# SW6208_A_A_C_LED__188.net
KiCad netlist of a schematic drawn in Altium Designer
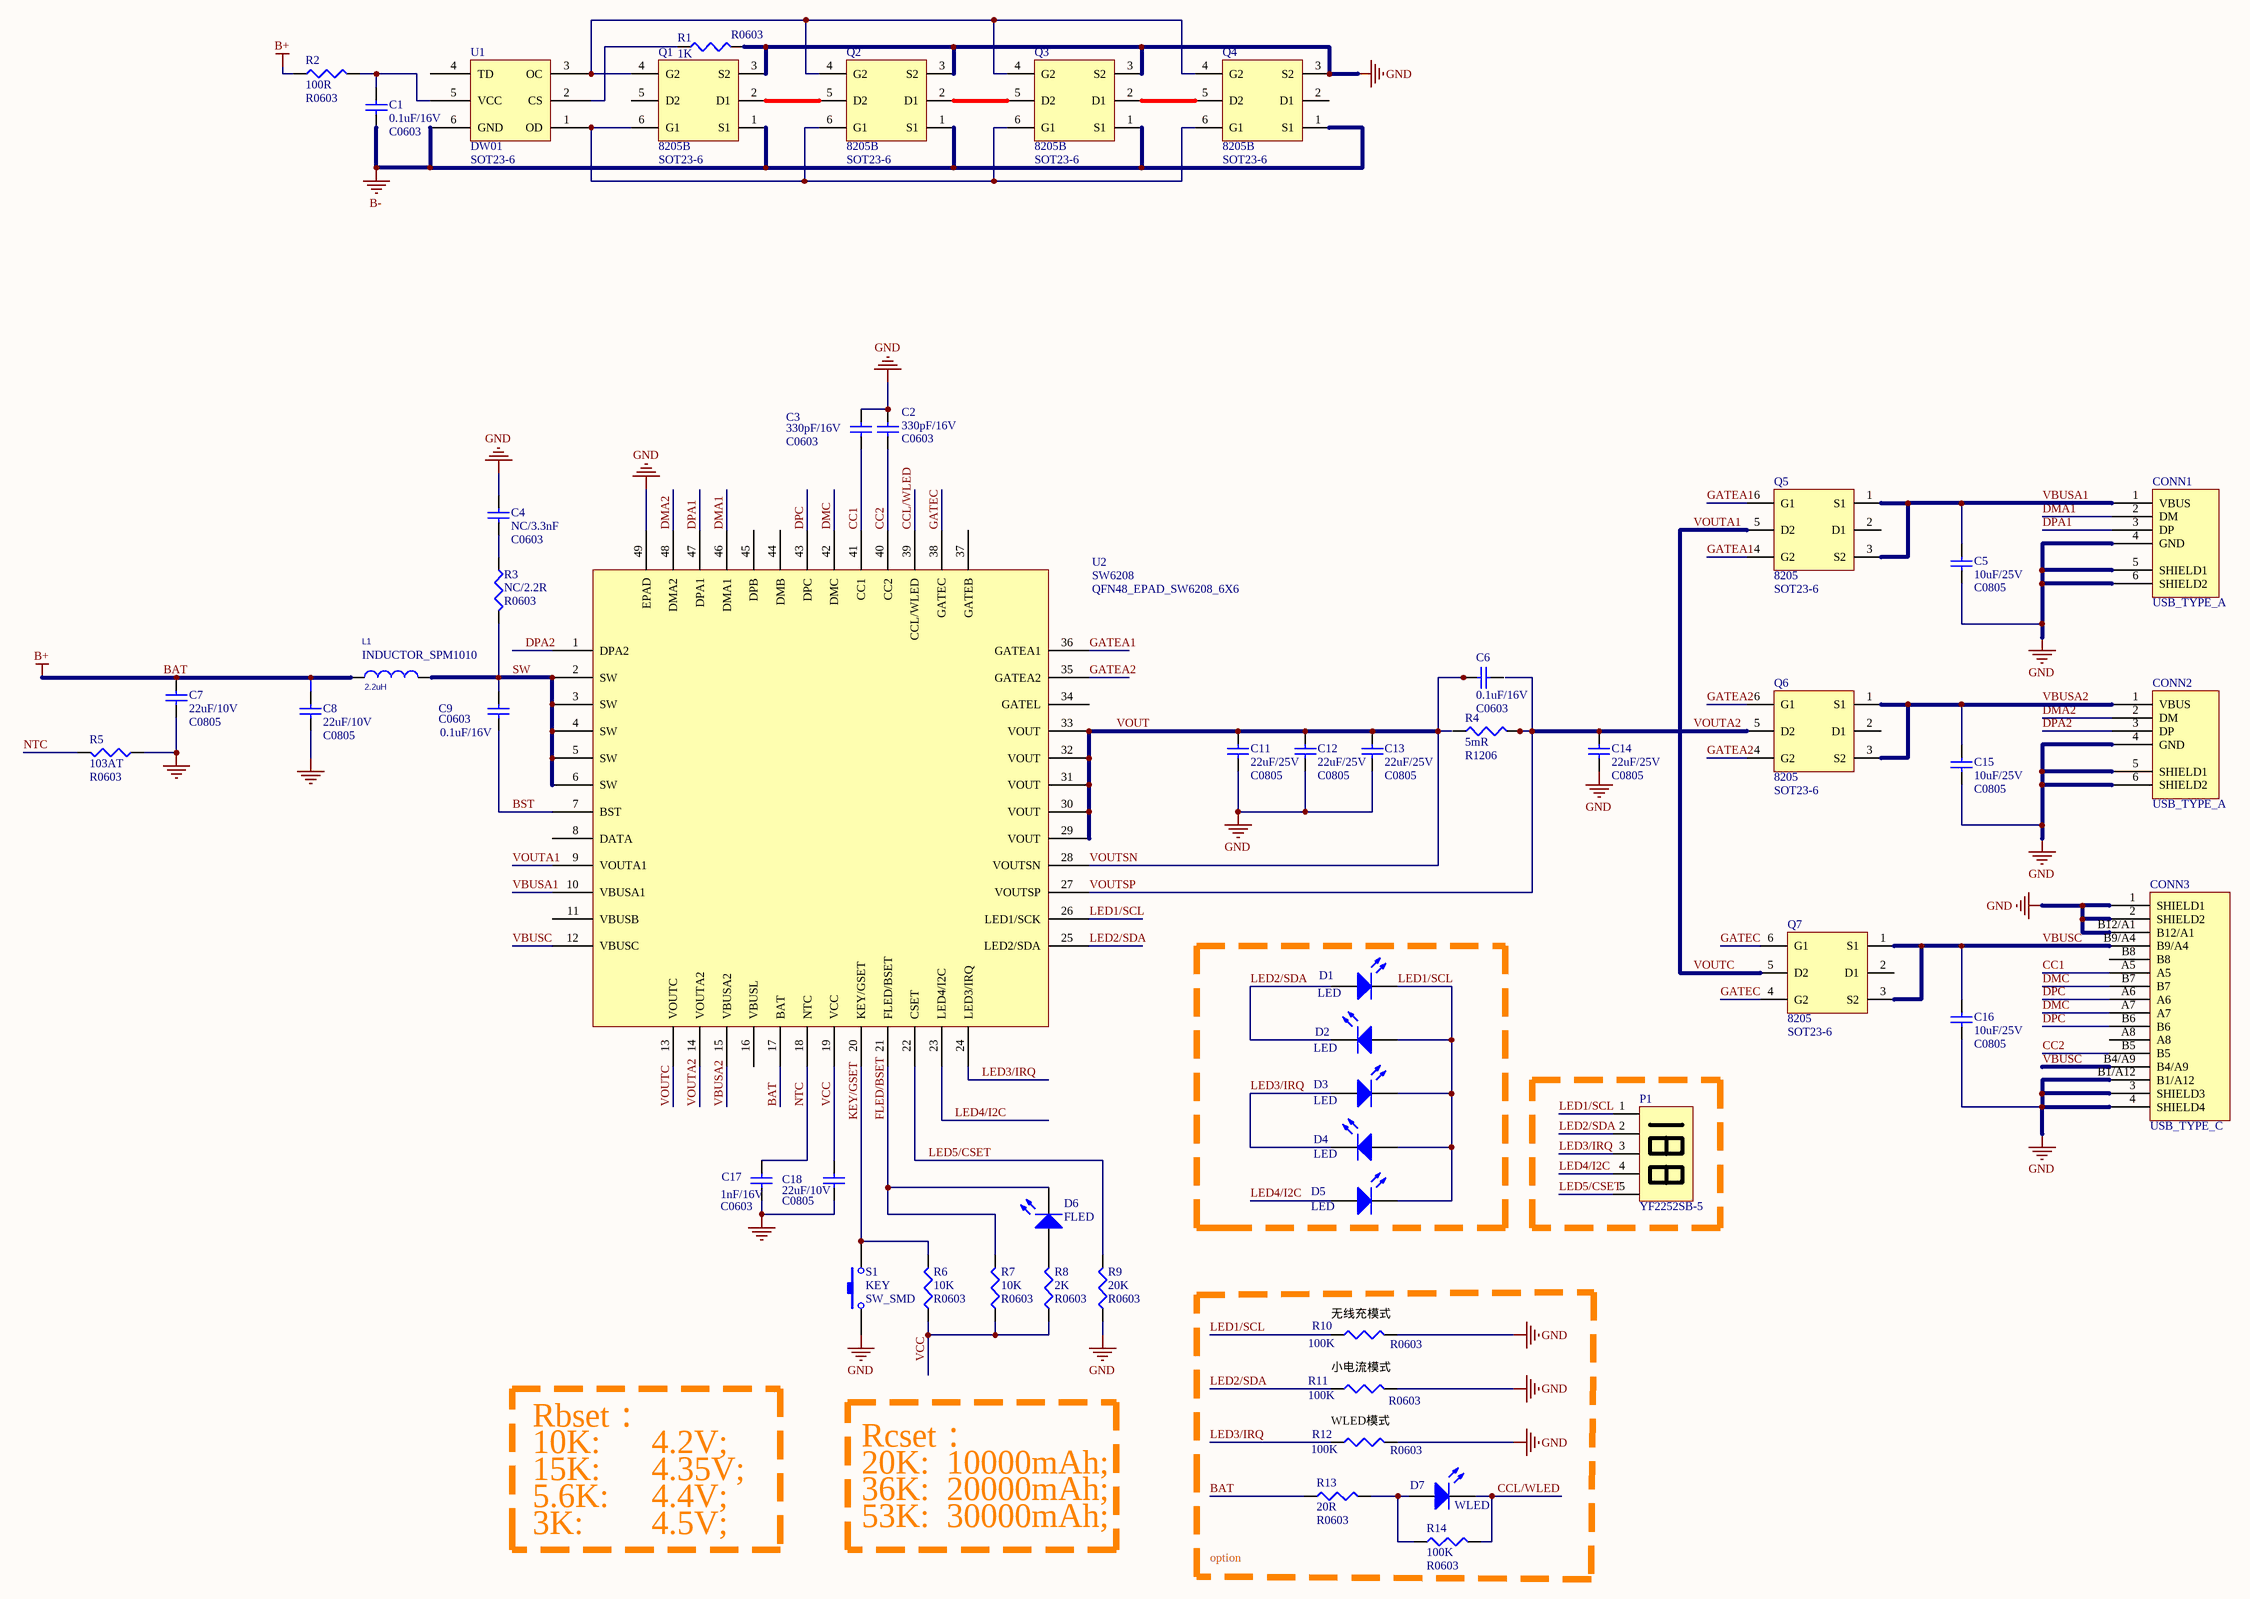
[diagram p0: SW6208+A+A+C+LED_普通188数码管.SchDoc]

(export (version "E")
  (design (tool "Eeschema 10.0.6"))
  (components
    (comp (ref "C1")
      (value "0.1uF/16V")
      (footprint "C0603")
      (description "Capacitor")
      (fields (field (name "PUBLISHER") "Altium Limited"))
      (libsource (lib "参考设计器件原理图更新") (part "CAP0603"))
    )
    (comp (ref "C2")
      (value "330pF/16V")
      (footprint "C0603")
      (description "Capacitor")
      (fields (field (name "PUBLISHER") "Altium Limited"))
      (libsource (lib "参考设计器件原理图更新") (part "CAP0603"))
    )
    (comp (ref "C3")
      (value "330pF/16V")
      (footprint "C0603")
      (description "Capacitor")
      (fields (field (name "PUBLISHER") "Altium Limited"))
      (libsource (lib "参考设计器件原理图更新") (part "CAP0603"))
    )
    (comp (ref "C4")
      (value "NC/3.3nF")
      (footprint "C0603")
      (description "Capacitor")
      (fields (field (name "PUBLISHER") "Altium Limited"))
      (libsource (lib "参考设计器件原理图更新") (part "CAP0603"))
    )
    (comp (ref "C5")
      (value "10uF/25V")
      (footprint "C0805")
      (description "Capacitor")
      (fields (field (name "PUBLISHER") "Altium Limited"))
      (libsource (lib "参考设计器件原理图更新") (part "CAP0805"))
    )
    (comp (ref "C6")
      (value "0.1uF/16V")
      (footprint "C0603")
      (description "Capacitor")
      (fields (field (name "PUBLISHER") "Altium Limited"))
      (libsource (lib "参考设计器件原理图更新") (part "CAP0603"))
    )
    (comp (ref "C7")
      (value "22uF/10V")
      (footprint "C0805")
      (description "Capacitor")
      (fields (field (name "PUBLISHER") "Altium Limited"))
      (libsource (lib "参考设计器件原理图更新") (part "CAP0805"))
    )
    (comp (ref "C8")
      (value "22uF/10V")
      (footprint "C0805")
      (description "Capacitor")
      (fields (field (name "PUBLISHER") "Altium Limited"))
      (libsource (lib "参考设计器件原理图更新") (part "CAP0805"))
    )
    (comp (ref "C9")
      (value "0.1uF/16V")
      (footprint "C0603")
      (description "Capacitor")
      (fields (field (name "PUBLISHER") "Altium Limited"))
      (libsource (lib "参考设计器件原理图更新") (part "CAP0603"))
    )
    (comp (ref "C11")
      (value "22uF/25V")
      (footprint "C0805")
      (description "Capacitor")
      (fields (field (name "PUBLISHER") "Altium Limited"))
      (libsource (lib "参考设计器件原理图更新") (part "CAP0805"))
    )
    (comp (ref "C12")
      (value "22uF/25V")
      (footprint "C0805")
      (description "Capacitor")
      (fields (field (name "PUBLISHER") "Altium Limited"))
      (libsource (lib "参考设计器件原理图更新") (part "CAP0805"))
    )
    (comp (ref "C13")
      (value "22uF/25V")
      (footprint "C0805")
      (description "Capacitor")
      (fields (field (name "PUBLISHER") "Altium Limited"))
      (libsource (lib "参考设计器件原理图更新") (part "CAP0805"))
    )
    (comp (ref "C14")
      (value "22uF/25V")
      (footprint "C0805")
      (description "Capacitor")
      (fields (field (name "PUBLISHER") "Altium Limited"))
      (libsource (lib "参考设计器件原理图更新") (part "CAP0805"))
    )
    (comp (ref "C15")
      (value "10uF/25V")
      (footprint "C0805")
      (description "Capacitor")
      (fields (field (name "PUBLISHER") "Altium Limited"))
      (libsource (lib "参考设计器件原理图更新") (part "CAP0805"))
    )
    (comp (ref "C16")
      (value "10uF/25V")
      (footprint "C0805")
      (description "Capacitor")
      (fields (field (name "PUBLISHER") "Altium Limited"))
      (libsource (lib "参考设计器件原理图更新") (part "CAP0805"))
    )
    (comp (ref "C17")
      (value "1nF/16V")
      (footprint "C0603")
      (description "Capacitor")
      (fields (field (name "PUBLISHER") "Altium Limited"))
      (libsource (lib "参考设计器件原理图更新") (part "CAP0603"))
    )
    (comp (ref "C18")
      (value "22uF/10V")
      (footprint "C0805")
      (description "Capacitor")
      (fields (field (name "PUBLISHER") "Altium Limited"))
      (libsource (lib "参考设计器件原理图更新") (part "CAP0805"))
    )
    (comp (ref "CONN1")
      (value "USB_TYPE_A")
      (footprint "USB_TYPE_A")
      (libsource (lib "参考设计器件原理图更新") (part "USB_TYPE_A"))
    )
    (comp (ref "CONN2")
      (value "USB_TYPE_A")
      (footprint "USB_TYPE_A")
      (libsource (lib "参考设计器件原理图更新") (part "USB_TYPE_A"))
    )
    (comp (ref "CONN3")
      (value "USB_TYPE_C")
      (footprint "LOUISAD:USB_TYPE_C")
      (libsource (lib "参考设计器件原理图更新") (part "USB_TYPE_C"))
    )
    (comp (ref "D1")
      (value "LED")
      (footprint "LED0603")
      (fields (field (name "PUBLISHER") "Altium Limited"))
      (libsource (lib "参考设计器件原理图更新") (part "LED_0603"))
    )
    (comp (ref "D2")
      (value "LED")
      (footprint "LED0603")
      (fields (field (name "PUBLISHER") "Altium Limited"))
      (libsource (lib "参考设计器件原理图更新") (part "LED_0603"))
    )
    (comp (ref "D3")
      (value "LED")
      (footprint "LED0603")
      (fields (field (name "PUBLISHER") "Altium Limited"))
      (libsource (lib "参考设计器件原理图更新") (part "LED_0603"))
    )
    (comp (ref "D4")
      (value "LED")
      (footprint "LED0603")
      (fields (field (name "PUBLISHER") "Altium Limited"))
      (libsource (lib "参考设计器件原理图更新") (part "LED_0603"))
    )
    (comp (ref "D5")
      (value "LED")
      (footprint "LED0603")
      (fields (field (name "PUBLISHER") "Altium Limited"))
      (libsource (lib "参考设计器件原理图更新") (part "LED_0603"))
    )
    (comp (ref "D6")
      (value "FLED")
      (footprint "LED0603")
      (description "LED")
      (fields (field (name "PUBLISHER") "Altium Limited"))
      (libsource (lib "参考设计器件原理图更新") (part "LED_0603"))
    )
    (comp (ref "D7")
      (value "WLED")
      (footprint "LED_5MM")
      (fields (field (name "PUBLISHER") "Altium Limited"))
      (libsource (lib "参考设计器件原理图更新") (part "WLED"))
    )
    (comp (ref "L1")
      (value "2.2uH")
      (footprint "INDUCTOR_SPM1010")
      (description "INDUCTOR")
      (libsource (lib "参考设计器件原理图更新") (part "INDUCTOR_SPM1010"))
    )
    (comp (ref "P1")
      (value "YF2252SB-5")
      (footprint "LED_Display_5")
      (description "188_LED_Display")
      (libsource (lib "参考设计器件原理图更新") (part "LED_Display_5"))
    )
    (comp (ref "Q1")
      (value "8205B")
      (footprint "SOT23-6")
      (description "NMOS")
      (fields (field (name "FOOTPRINF") "SOT23-6"))
      (libsource (lib "") (part "8205_1"))
    )
    (comp (ref "Q2")
      (value "8205B")
      (footprint "SOT23-6")
      (description "NMOS")
      (fields (field (name "FOOTPRINF") "SOT23-6"))
      (libsource (lib "") (part "8205_1"))
    )
    (comp (ref "Q3")
      (value "8205B")
      (footprint "SOT23-6")
      (description "NMOS")
      (fields (field (name "FOOTPRINF") "SOT23-6"))
      (libsource (lib "") (part "8205_1"))
    )
    (comp (ref "Q4")
      (value "8205B")
      (footprint "SOT23-6")
      (description "NMOS")
      (fields (field (name "FOOTPRINF") "SOT23-6"))
      (libsource (lib "") (part "8205_1"))
    )
    (comp (ref "Q5")
      (value "8205")
      (footprint "SOT23-6")
      (description "NMOS")
      (fields (field (name "FOOTPRINF") "SOT23-6"))
      (libsource (lib "参考设计器件原理图更新") (part "8205"))
    )
    (comp (ref "Q6")
      (value "8205")
      (footprint "SOT23-6")
      (description "NMOS")
      (fields (field (name "FOOTPRINF") "SOT23-6"))
      (libsource (lib "参考设计器件原理图更新") (part "8205"))
    )
    (comp (ref "Q7")
      (value "8205")
      (footprint "SOT23-6")
      (description "NMOS")
      (fields (field (name "FOOTPRINF") "SOT23-6"))
      (libsource (lib "参考设计器件原理图更新") (part "8205"))
    )
    (comp (ref "R1")
      (value "1K")
      (footprint "R0603")
      (description "Resistor")
      (fields (field (name "PUBLISHER") "Altium Limited"))
      (libsource (lib "参考设计器件原理图更新") (part "RES_0603"))
    )
    (comp (ref "R2")
      (value "100R")
      (footprint "R0603")
      (description "Resistor")
      (fields (field (name "PUBLISHER") "Altium Limited"))
      (libsource (lib "参考设计器件原理图更新") (part "RES_0603"))
    )
    (comp (ref "R3")
      (value "NC/2.2R")
      (footprint "R0603")
      (description "Resistor")
      (fields (field (name "PUBLISHER") "Altium Limited"))
      (libsource (lib "参考设计器件原理图更新") (part "RES_0603"))
    )
    (comp (ref "R4")
      (value "5mR")
      (footprint "R1206")
      (description "Resistor")
      (fields (field (name "PUBLISHER") "Altium Limited"))
      (libsource (lib "参考设计器件原理图更新") (part "RES_1206"))
    )
    (comp (ref "R5")
      (value "103AT")
      (footprint "R0603")
      (description "Resistor")
      (fields (field (name "PUBLISHER") "Altium Limited"))
      (libsource (lib "参考设计器件原理图更新") (part "RES_0603"))
    )
    (comp (ref "R6")
      (value "10K")
      (footprint "R0603")
      (description "Resistor")
      (fields (field (name "PUBLISHER") "Altium Limited"))
      (libsource (lib "参考设计器件原理图更新") (part "RES_0603"))
    )
    (comp (ref "R7")
      (value "10K")
      (footprint "R0603")
      (description "Resistor")
      (fields (field (name "PUBLISHER") "Altium Limited"))
      (libsource (lib "参考设计器件原理图更新") (part "RES_0603"))
    )
    (comp (ref "R8")
      (value "2K")
      (footprint "R0603")
      (description "Resistor")
      (fields (field (name "PUBLISHER") "Altium Limited"))
      (libsource (lib "参考设计器件原理图更新") (part "RES_0603"))
    )
    (comp (ref "R9")
      (value "20K")
      (footprint "R0603")
      (description "Resistor")
      (fields (field (name "PUBLISHER") "Altium Limited"))
      (libsource (lib "参考设计器件原理图更新") (part "RES_0603"))
    )
    (comp (ref "R10")
      (value "100K")
      (footprint "R0603")
      (description "Resistor")
      (fields (field (name "PUBLISHER") "Altium Limited"))
      (libsource (lib "参考设计器件原理图更新") (part "RES_0603"))
    )
    (comp (ref "R11")
      (value "100K")
      (footprint "R0603")
      (description "Resistor")
      (fields (field (name "PUBLISHER") "Altium Limited"))
      (libsource (lib "参考设计器件原理图更新") (part "RES_0603"))
    )
    (comp (ref "R12")
      (value "100K")
      (footprint "R0603")
      (description "Resistor")
      (fields (field (name "PUBLISHER") "Altium Limited"))
      (libsource (lib "参考设计器件原理图更新") (part "RES_0603"))
    )
    (comp (ref "R13")
      (value "20R")
      (footprint "R0603")
      (description "Resistor")
      (fields (field (name "PUBLISHER") "Altium Limited"))
      (libsource (lib "参考设计器件原理图更新") (part "RES_0603"))
    )
    (comp (ref "R14")
      (value "100K")
      (footprint "R0603")
      (description "Resistor")
      (fields (field (name "PUBLISHER") "Altium Limited"))
      (libsource (lib "参考设计器件原理图更新") (part "RES_0603"))
    )
    (comp (ref "S1")
      (value "KEY")
      (footprint "SW_SMD")
      (fields (field (name "FOOTPRINF") "SW_SMD"))
      (libsource (lib "参考设计器件原理图更新") (part "SW K"))
    )
    (comp (ref "U1")
      (value "DW01")
      (footprint "SOT23-6")
      (description "BAT_PROTECT_IC")
      (libsource (lib "参考设计器件原理图更新") (part "DW01"))
    )
    (comp (ref "U2")
      (value "SW6208")
      (footprint "QFN48_EPAD_SW6208_6X6")
      (description "IC")
      (libsource (lib "芯片型号原理图") (part "SW6208"))
    )
  )
  (nets
    (net (code "1") (name "/BST") (class "Default")
      (node (ref "C9") (pin "1") (pinfunction "1_1") (pintype "passive"))
      (node (ref "U2") (pin "7") (pinfunction "BST_7") (pintype "passive"))
    )
    (net (code "2") (name "/CC1") (class "Default")
      (node (ref "C3") (pin "1") (pinfunction "1_1") (pintype "passive"))
      (node (ref "CONN3") (pin "A5") (pinfunction "A5_A5") (pintype "passive"))
      (node (ref "U2") (pin "41") (pinfunction "CC1_41") (pintype "passive"))
    )
    (net (code "3") (name "/CC2") (class "Default")
      (node (ref "C2") (pin "1") (pinfunction "1_1") (pintype "passive"))
      (node (ref "CONN3") (pin "B5") (pinfunction "B5_B5") (pintype "passive"))
      (node (ref "U2") (pin "40") (pinfunction "CC2_40") (pintype "passive"))
    )
    (net (code "4") (name "/CCL{slash}WLED") (class "Default")
      (node (ref "D7") (pin "2") (pinfunction "K_2") (pintype "passive"))
      (node (ref "R14") (pin "2") (pinfunction "2_2") (pintype "passive"))
      (node (ref "U2") (pin "39") (pinfunction "CCL/WLED_39") (pintype "passive"))
    )
    (net (code "5") (name "/DMA1") (class "Default")
      (node (ref "CONN1") (pin "2") (pinfunction "DM_2") (pintype "passive"))
      (node (ref "U2") (pin "46") (pinfunction "DMA1_46") (pintype "passive"))
    )
    (net (code "6") (name "/DMA2") (class "Default")
      (node (ref "CONN2") (pin "2") (pinfunction "DM_2") (pintype "passive"))
      (node (ref "U2") (pin "48") (pinfunction "DMA2_48") (pintype "passive"))
    )
    (net (code "7") (name "/DMC") (class "Default")
      (node (ref "CONN3") (pin "A7") (pinfunction "A7_A7") (pintype "passive"))
      (node (ref "CONN3") (pin "B7") (pinfunction "B7_B7") (pintype "passive"))
      (node (ref "U2") (pin "42") (pinfunction "DMC_42") (pintype "passive"))
    )
    (net (code "8") (name "/DPA1") (class "Default")
      (node (ref "CONN1") (pin "3") (pinfunction "DP_3") (pintype "passive"))
      (node (ref "U2") (pin "47") (pinfunction "DPA1_47") (pintype "passive"))
    )
    (net (code "9") (name "/DPA2") (class "Default")
      (node (ref "CONN2") (pin "3") (pinfunction "DP_3") (pintype "passive"))
      (node (ref "U2") (pin "1") (pinfunction "DPA2_1") (pintype "passive"))
    )
    (net (code "10") (name "/DPC") (class "Default")
      (node (ref "CONN3") (pin "A6") (pinfunction "A6_A6") (pintype "passive"))
      (node (ref "CONN3") (pin "B6") (pinfunction "B6_B6") (pintype "passive"))
      (node (ref "U2") (pin "43") (pinfunction "DPC_43") (pintype "passive"))
    )
    (net (code "11") (name "/FLED{slash}BSET") (class "Default")
      (node (ref "D6") (pin "2") (pinfunction "K_2") (pintype "passive"))
      (node (ref "R7") (pin "2") (pinfunction "2_2") (pintype "passive"))
      (node (ref "U2") (pin "21") (pinfunction "FLED/BSET_21") (pintype "passive"))
    )
    (net (code "12") (name "/GATEA1") (class "Default")
      (node (ref "Q5") (pin "4") (pinfunction "G2_4") (pintype "passive"))
      (node (ref "Q5") (pin "6") (pinfunction "G1_6") (pintype "passive"))
      (node (ref "U2") (pin "36") (pinfunction "GATEA1_36") (pintype "passive"))
    )
    (net (code "13") (name "/GATEA2") (class "Default")
      (node (ref "Q6") (pin "4") (pinfunction "G2_4") (pintype "passive"))
      (node (ref "Q6") (pin "6") (pinfunction "G1_6") (pintype "passive"))
      (node (ref "U2") (pin "35") (pinfunction "GATEA2_35") (pintype "passive"))
    )
    (net (code "14") (name "/GATEC") (class "Default")
      (node (ref "Q7") (pin "4") (pinfunction "G2_4") (pintype "passive"))
      (node (ref "Q7") (pin "6") (pinfunction "G1_6") (pintype "passive"))
      (node (ref "U2") (pin "38") (pinfunction "GATEC_38") (pintype "passive"))
    )
    (net (code "15") (name "/KEY{slash}GSET") (class "Default")
      (node (ref "R6") (pin "2") (pinfunction "2_2") (pintype "passive"))
      (node (ref "S1") (pin "2") (pinfunction "2_2") (pintype "passive"))
      (node (ref "U2") (pin "20") (pinfunction "KEY/GSET_20") (pintype "passive"))
    )
    (net (code "16") (name "/LED1{slash}SCL") (class "Default")
      (node (ref "D1") (pin "2") (pinfunction "K_2") (pintype "passive"))
      (node (ref "D2") (pin "1") (pinfunction "A_1") (pintype "passive"))
      (node (ref "D3") (pin "2") (pinfunction "K_2") (pintype "passive"))
      (node (ref "D4") (pin "1") (pinfunction "A_1") (pintype "passive"))
      (node (ref "D5") (pin "2") (pinfunction "K_2") (pintype "passive"))
      (node (ref "P1") (pin "1") (pinfunction "F_1") (pintype "passive"))
      (node (ref "R10") (pin "1") (pinfunction "1_1") (pintype "passive"))
      (node (ref "U2") (pin "26") (pinfunction "LED1/SCK_26") (pintype "passive"))
    )
    (net (code "17") (name "/LED2{slash}SDA") (class "Default")
      (node (ref "D1") (pin "1") (pinfunction "A_1") (pintype "passive"))
      (node (ref "D2") (pin "2") (pinfunction "K_2") (pintype "passive"))
      (node (ref "P1") (pin "2") (pinfunction "C_2") (pintype "passive"))
      (node (ref "R11") (pin "1") (pinfunction "1_1") (pintype "passive"))
      (node (ref "U2") (pin "25") (pinfunction "LED2/SDA_25") (pintype "passive"))
    )
    (net (code "18") (name "/LED3{slash}IRQ") (class "Default")
      (node (ref "D3") (pin "1") (pinfunction "A_1") (pintype "passive"))
      (node (ref "D4") (pin "2") (pinfunction "K_2") (pintype "passive"))
      (node (ref "P1") (pin "3") (pinfunction "D_3") (pintype "passive"))
      (node (ref "R12") (pin "1") (pinfunction "1_1") (pintype "passive"))
      (node (ref "U2") (pin "24") (pinfunction "LED3/IRQ_24") (pintype "passive"))
    )
    (net (code "19") (name "/LED4{slash}I2C") (class "Default")
      (node (ref "D5") (pin "1") (pinfunction "A_1") (pintype "passive"))
      (node (ref "P1") (pin "4") (pinfunction "E_4") (pintype "passive"))
      (node (ref "U2") (pin "23") (pinfunction "LED4/I2C_23") (pintype "passive"))
    )
    (net (code "20") (name "/LED5{slash}CSET") (class "Default")
      (node (ref "P1") (pin "5") (pinfunction "G_5") (pintype "passive"))
      (node (ref "R9") (pin "2") (pinfunction "2_2") (pintype "passive"))
      (node (ref "U2") (pin "22") (pinfunction "CSET_22") (pintype "passive"))
    )
    (net (code "21") (name "/NTC") (class "Default")
      (node (ref "C17") (pin "1") (pinfunction "1_1") (pintype "passive"))
      (node (ref "R5") (pin "2") (pinfunction "2_2") (pintype "passive"))
      (node (ref "U2") (pin "18") (pinfunction "NTC_18") (pintype "passive"))
    )
    (net (code "22") (name "/SW") (class "Default")
      (node (ref "C9") (pin "2") (pinfunction "2_2") (pintype "passive"))
      (node (ref "L1") (pin "2") (pinfunction "2_2") (pintype "passive"))
      (node (ref "R3") (pin "2") (pinfunction "2_2") (pintype "passive"))
      (node (ref "U2") (pin "2") (pinfunction "SW_2") (pintype "passive"))
      (node (ref "U2") (pin "3") (pinfunction "SW_3") (pintype "passive"))
      (node (ref "U2") (pin "4") (pinfunction "SW_4") (pintype "passive"))
      (node (ref "U2") (pin "5") (pinfunction "SW_5") (pintype "passive"))
      (node (ref "U2") (pin "6") (pinfunction "SW_6") (pintype "passive"))
    )
    (net (code "23") (name "/VBUSA1") (class "Default")
      (node (ref "C5") (pin "2") (pinfunction "2_2") (pintype "passive"))
      (node (ref "CONN1") (pin "1") (pinfunction "VBUS_1") (pintype "passive"))
      (node (ref "Q5") (pin "1") (pinfunction "S1_1") (pintype "passive"))
      (node (ref "Q5") (pin "3") (pinfunction "S2_3") (pintype "passive"))
      (node (ref "U2") (pin "10") (pinfunction "VBUSA1_10") (pintype "passive"))
    )
    (net (code "24") (name "/VBUSA2") (class "Default")
      (node (ref "C15") (pin "2") (pinfunction "2_2") (pintype "passive"))
      (node (ref "CONN2") (pin "1") (pinfunction "VBUS_1") (pintype "passive"))
      (node (ref "Q6") (pin "1") (pinfunction "S1_1") (pintype "passive"))
      (node (ref "Q6") (pin "3") (pinfunction "S2_3") (pintype "passive"))
      (node (ref "U2") (pin "15") (pinfunction "VBUSA2_15") (pintype "passive"))
    )
    (net (code "25") (name "/VBUSC") (class "Default")
      (node (ref "C16") (pin "2") (pinfunction "2_2") (pintype "passive"))
      (node (ref "CONN3") (pin "B4/A9") (pinfunction "B4/A9_B4/A9") (pintype "passive"))
      (node (ref "CONN3") (pin "B9/A4") (pinfunction "B9/A4_B9/A4") (pintype "passive"))
      (node (ref "Q7") (pin "1") (pinfunction "S1_1") (pintype "passive"))
      (node (ref "Q7") (pin "3") (pinfunction "S2_3") (pintype "passive"))
      (node (ref "U2") (pin "12") (pinfunction "VBUSC_12") (pintype "passive"))
    )
    (net (code "26") (name "/VCC") (class "Default")
      (node (ref "C18") (pin "1") (pinfunction "1_1") (pintype "passive"))
      (node (ref "R6") (pin "1") (pinfunction "1_1") (pintype "passive"))
      (node (ref "R7") (pin "1") (pinfunction "1_1") (pintype "passive"))
      (node (ref "R8") (pin "1") (pinfunction "1_1") (pintype "passive"))
      (node (ref "U2") (pin "19") (pinfunction "VCC_19") (pintype "passive"))
    )
    (net (code "27") (name "/VOUT") (class "Default")
      (node (ref "C11") (pin "2") (pinfunction "2_2") (pintype "passive"))
      (node (ref "C12") (pin "2") (pinfunction "2_2") (pintype "passive"))
      (node (ref "C13") (pin "2") (pinfunction "2_2") (pintype "passive"))
      (node (ref "C6") (pin "1") (pinfunction "1_1") (pintype "passive"))
      (node (ref "U2") (pin "28") (pinfunction "VOUTSN_28") (pintype "passive"))
      (node (ref "U2") (pin "29") (pinfunction "VOUT_29") (pintype "passive"))
      (node (ref "U2") (pin "30") (pinfunction "VOUT_30") (pintype "passive"))
      (node (ref "U2") (pin "31") (pinfunction "VOUT_31") (pintype "passive"))
      (node (ref "U2") (pin "32") (pinfunction "VOUT_32") (pintype "passive"))
      (node (ref "U2") (pin "33") (pinfunction "VOUT_33") (pintype "passive"))
    )
    (net (code "28") (name "/VOUTA1") (class "Default")
      (node (ref "Q5") (pin "5") (pinfunction "D2_5") (pintype "passive"))
      (node (ref "Q7") (pin "5") (pinfunction "D2_5") (pintype "passive"))
      (node (ref "U2") (pin "13") (pinfunction "VOUTC_13") (pintype "passive"))
      (node (ref "U2") (pin "9") (pinfunction "VOUTA1_9") (pintype "passive"))
    )
    (net (code "29") (name "/VOUTA2") (class "Default")
      (node (ref "C14") (pin "2") (pinfunction "2_2") (pintype "passive"))
      (node (ref "Q6") (pin "5") (pinfunction "D2_5") (pintype "passive"))
      (node (ref "R4") (pin "2") (pinfunction "2_2") (pintype "passive"))
      (node (ref "U2") (pin "14") (pinfunction "VOUTA2_14") (pintype "passive"))
      (node (ref "U2") (pin "27") (pinfunction "VOUTSP_27") (pintype "passive"))
    )
    (net (code "30") (name "B+") (class "Default")
      (node (ref "C7") (pin "2") (pinfunction "2_2") (pintype "passive"))
      (node (ref "C8") (pin "2") (pinfunction "2_2") (pintype "passive"))
      (node (ref "L1") (pin "1") (pinfunction "1_1") (pintype "passive"))
      (node (ref "R13") (pin "1") (pinfunction "1_1") (pintype "passive"))
      (node (ref "R2") (pin "1") (pinfunction "1_1") (pintype "passive"))
      (node (ref "U2") (pin "17") (pinfunction "BAT_17") (pintype "passive"))
    )
    (net (code "31") (name "B-") (class "Default")
      (node (ref "C1") (pin "1") (pinfunction "1_1") (pintype "passive"))
      (node (ref "Q1") (pin "1") (pinfunction "S1_1") (pintype "passive"))
      (node (ref "Q2") (pin "1") (pinfunction "S1_1") (pintype "passive"))
      (node (ref "Q3") (pin "1") (pinfunction "S1_1") (pintype "passive"))
      (node (ref "Q4") (pin "1") (pinfunction "S1_1") (pintype "passive"))
      (node (ref "U1") (pin "6") (pinfunction "GND_6") (pintype "passive"))
    )
    (net (code "32") (name "GND") (class "Default")
      (node (ref "C11") (pin "1") (pinfunction "1_1") (pintype "passive"))
      (node (ref "C12") (pin "1") (pinfunction "1_1") (pintype "passive"))
      (node (ref "C13") (pin "1") (pinfunction "1_1") (pintype "passive"))
      (node (ref "C14") (pin "1") (pinfunction "1_1") (pintype "passive"))
      (node (ref "C15") (pin "1") (pinfunction "1_1") (pintype "passive"))
      (node (ref "C16") (pin "1") (pinfunction "1_1") (pintype "passive"))
      (node (ref "C17") (pin "2") (pinfunction "2_2") (pintype "passive"))
      (node (ref "C18") (pin "2") (pinfunction "2_2") (pintype "passive"))
      (node (ref "C2") (pin "2") (pinfunction "2_2") (pintype "passive"))
      (node (ref "C3") (pin "2") (pinfunction "2_2") (pintype "passive"))
      (node (ref "C4") (pin "2") (pinfunction "2_2") (pintype "passive"))
      (node (ref "C5") (pin "1") (pinfunction "1_1") (pintype "passive"))
      (node (ref "C7") (pin "1") (pinfunction "1_1") (pintype "passive"))
      (node (ref "C8") (pin "1") (pinfunction "1_1") (pintype "passive"))
      (node (ref "CONN1") (pin "4") (pinfunction "GND_4") (pintype "passive"))
      (node (ref "CONN1") (pin "5") (pinfunction "SHIELD1_5") (pintype "passive"))
      (node (ref "CONN1") (pin "6") (pinfunction "SHIELD2_6") (pintype "passive"))
      (node (ref "CONN2") (pin "4") (pinfunction "GND_4") (pintype "passive"))
      (node (ref "CONN2") (pin "5") (pinfunction "SHIELD1_5") (pintype "passive"))
      (node (ref "CONN2") (pin "6") (pinfunction "SHIELD2_6") (pintype "passive"))
      (node (ref "CONN3") (pin "1") (pinfunction "SHIELD1_1") (pintype "passive"))
      (node (ref "CONN3") (pin "2") (pinfunction "SHIELD2_2") (pintype "passive"))
      (node (ref "CONN3") (pin "3") (pinfunction "SHIELD3_3") (pintype "passive"))
      (node (ref "CONN3") (pin "4") (pinfunction "SHIELD4_4") (pintype "passive"))
      (node (ref "CONN3") (pin "B1/A12") (pinfunction "B1/A12_B1/A12") (pintype "passive"))
      (node (ref "CONN3") (pin "B12/A1") (pinfunction "B12/A1_B12/A1") (pintype "passive"))
      (node (ref "Q1") (pin "3") (pinfunction "S2_3") (pintype "passive"))
      (node (ref "Q2") (pin "3") (pinfunction "S2_3") (pintype "passive"))
      (node (ref "Q3") (pin "3") (pinfunction "S2_3") (pintype "passive"))
      (node (ref "Q4") (pin "3") (pinfunction "S2_3") (pintype "passive"))
      (node (ref "R1") (pin "2") (pinfunction "2_2") (pintype "passive"))
      (node (ref "R10") (pin "2") (pinfunction "2_2") (pintype "passive"))
      (node (ref "R11") (pin "2") (pinfunction "2_2") (pintype "passive"))
      (node (ref "R12") (pin "2") (pinfunction "2_2") (pintype "passive"))
      (node (ref "R5") (pin "1") (pinfunction "1_1") (pintype "passive"))
      (node (ref "R9") (pin "1") (pinfunction "1_1") (pintype "passive"))
      (node (ref "S1") (pin "1") (pinfunction "1_1") (pintype "passive"))
      (node (ref "U2") (pin "49") (pinfunction "EPAD_49") (pintype "passive"))
    )
    (net (code "33") (name "Net-(C4-Pad1)") (class "Default")
      (node (ref "C4") (pin "1") (pinfunction "1_1") (pintype "passive"))
      (node (ref "R3") (pin "1") (pinfunction "1_1") (pintype "passive"))
    )
    (net (code "34") (name "Net-(D6-A)") (class "Default")
      (node (ref "D6") (pin "1") (pinfunction "A_1") (pintype "passive"))
      (node (ref "R8") (pin "2") (pinfunction "2_2") (pintype "passive"))
    )
    (net (code "35") (name "Net-(D7-A)") (class "Default")
      (node (ref "D7") (pin "1") (pinfunction "A_1") (pintype "passive"))
      (node (ref "R13") (pin "2") (pinfunction "2_2") (pintype "passive"))
      (node (ref "R14") (pin "1") (pinfunction "1_1") (pintype "passive"))
    )
    (net (code "36") (name "Net-(Q1-D1)") (class "Default")
      (node (ref "Q1") (pin "2") (pinfunction "D1_2") (pintype "passive"))
      (node (ref "Q2") (pin "5") (pinfunction "D2_5") (pintype "passive"))
    )
    (net (code "37") (name "Net-(Q1-G1)") (class "Default")
      (node (ref "Q1") (pin "6") (pinfunction "G1_6") (pintype "passive"))
      (node (ref "Q2") (pin "6") (pinfunction "G1_6") (pintype "passive"))
      (node (ref "Q3") (pin "6") (pinfunction "G1_6") (pintype "passive"))
      (node (ref "Q4") (pin "6") (pinfunction "G1_6") (pintype "passive"))
      (node (ref "U1") (pin "1") (pinfunction "OD_1") (pintype "passive"))
    )
    (net (code "38") (name "Net-(Q1-G2)") (class "Default")
      (node (ref "Q1") (pin "4") (pinfunction "G2_4") (pintype "passive"))
      (node (ref "Q2") (pin "4") (pinfunction "G2_4") (pintype "passive"))
      (node (ref "Q3") (pin "4") (pinfunction "G2_4") (pintype "passive"))
      (node (ref "Q4") (pin "4") (pinfunction "G2_4") (pintype "passive"))
      (node (ref "U1") (pin "3") (pinfunction "OC_3") (pintype "passive"))
    )
    (net (code "39") (name "Net-(Q2-D1)") (class "Default")
      (node (ref "Q2") (pin "2") (pinfunction "D1_2") (pintype "passive"))
      (node (ref "Q3") (pin "5") (pinfunction "D2_5") (pintype "passive"))
    )
    (net (code "40") (name "Net-(Q3-D1)") (class "Default")
      (node (ref "Q3") (pin "2") (pinfunction "D1_2") (pintype "passive"))
      (node (ref "Q4") (pin "5") (pinfunction "D2_5") (pintype "passive"))
    )
    (net (code "41") (name "Net-(U1-CS)") (class "Default")
      (node (ref "R1") (pin "1") (pinfunction "1_1") (pintype "passive"))
      (node (ref "U1") (pin "2") (pinfunction "CS_2") (pintype "passive"))
    )
    (net (code "42") (name "Net-(U1-VCC)") (class "Default")
      (node (ref "C1") (pin "2") (pinfunction "2_2") (pintype "passive"))
      (node (ref "R2") (pin "2") (pinfunction "2_2") (pintype "passive"))
      (node (ref "U1") (pin "5") (pinfunction "VCC_5") (pintype "passive"))
    )
    (net (code "43") (name "unconnected-(C6-Pad2)") (class "Default")
      (node (ref "C6") (pin "2") (pinfunction "2_2") (pintype "passive"))
    )
    (net (code "44") (name "unconnected-(CONN3-PadA8)") (class "Default")
      (node (ref "CONN3") (pin "A8") (pinfunction "A8_A8") (pintype "passive"))
    )
    (net (code "45") (name "unconnected-(CONN3-PadB8)") (class "Default")
      (node (ref "CONN3") (pin "B8") (pinfunction "B8_B8") (pintype "passive"))
    )
    (net (code "46") (name "unconnected-(Q1-D2-Pad5)") (class "Default")
      (node (ref "Q1") (pin "5") (pinfunction "D2_5") (pintype "passive"))
    )
    (net (code "47") (name "unconnected-(Q4-D1-Pad2)") (class "Default")
      (node (ref "Q4") (pin "2") (pinfunction "D1_2") (pintype "passive"))
    )
    (net (code "48") (name "unconnected-(Q5-D1-Pad2)") (class "Default")
      (node (ref "Q5") (pin "2") (pinfunction "D1_2") (pintype "passive"))
    )
    (net (code "49") (name "unconnected-(Q6-D1-Pad2)") (class "Default")
      (node (ref "Q6") (pin "2") (pinfunction "D1_2") (pintype "passive"))
    )
    (net (code "50") (name "unconnected-(Q7-D1-Pad2)") (class "Default")
      (node (ref "Q7") (pin "2") (pinfunction "D1_2") (pintype "passive"))
    )
    (net (code "51") (name "unconnected-(R4-Pad1)") (class "Default")
      (node (ref "R4") (pin "1") (pinfunction "1_1") (pintype "passive"))
    )
    (net (code "52") (name "unconnected-(U1-TD-Pad4)") (class "Default")
      (node (ref "U1") (pin "4") (pinfunction "TD_4") (pintype "passive"))
    )
    (net (code "53") (name "unconnected-(U2-DATA-Pad8)") (class "Default")
      (node (ref "U2") (pin "8") (pinfunction "DATA_8") (pintype "passive"))
    )
    (net (code "54") (name "unconnected-(U2-DMB-Pad44)") (class "Default")
      (node (ref "U2") (pin "44") (pinfunction "DMB_44") (pintype "passive"))
    )
    (net (code "55") (name "unconnected-(U2-DPB-Pad45)") (class "Default")
      (node (ref "U2") (pin "45") (pinfunction "DPB_45") (pintype "passive"))
    )
    (net (code "56") (name "unconnected-(U2-GATEB-Pad37)") (class "Default")
      (node (ref "U2") (pin "37") (pinfunction "GATEB_37") (pintype "passive"))
    )
    (net (code "57") (name "unconnected-(U2-GATEL-Pad34)") (class "Default")
      (node (ref "U2") (pin "34") (pinfunction "GATEL_34") (pintype "passive"))
    )
    (net (code "58") (name "unconnected-(U2-VBUSB-Pad11)") (class "Default")
      (node (ref "U2") (pin "11") (pinfunction "VBUSB_11") (pintype "passive"))
    )
    (net (code "59") (name "unconnected-(U2-VBUSL-Pad16)") (class "Default")
      (node (ref "U2") (pin "16") (pinfunction "VBUSL_16") (pintype "passive"))
    )
  )
)
